# ina226-breakout.net
KiCad netlist of a schematic drawn in EAGLE
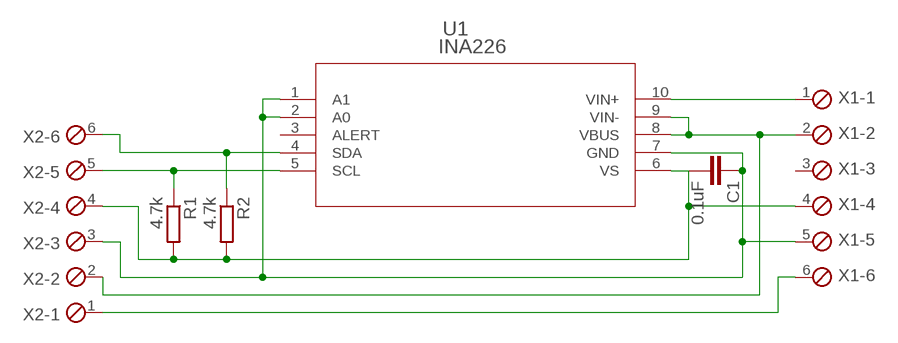
[diagram p0: schematic, sheet 1]

(export (version "E")
  (design (tool "Eeschema 10.0.6"))
  (components
    (comp (ref "C1")
      (value "0.1uF")
      (footprint "eagle-import:C0603")
      (libsource (lib "eagle-import") (part "C-EUC0603"))
    )
    (comp (ref "R1")
      (value "4.7k")
      (footprint "eagle-import:R0603")
      (libsource (lib "eagle-import") (part "R-EU_R0603"))
    )
    (comp (ref "R2")
      (value "4.7k")
      (footprint "eagle-import:R0603")
      (libsource (lib "eagle-import") (part "R-EU_R0603"))
    )
    (comp (ref "U1")
      (value "INA226")
      (footprint "eagle-import:DGS10")
      (fields
        (field (name "MANUFACTURER_PART_NUMBER") "INA226AIDGSR")
        (field (name "MANUFACTURER_PART_NUMBER_1") "INA226")
        (field (name "COPYRIGHT") "Copyright (C) 2022 Ultra Librarian. All rights reserved.")
      )
      (libsource (lib "eagle-import") (part "INA226AIDGSR"))
    )
    (comp (ref "X1")
      (value "MPT6")
      (footprint "eagle-import:6POL254")
      (libsource (lib "eagle-import") (part "MPT6"))
    )
    (comp (ref "X2")
      (value "MPT6")
      (footprint "eagle-import:6POL254")
      (libsource (lib "eagle-import") (part "MPT6"))
    )
  )
  (nets
    (net (code "1") (name "Net-(U1-A0)") (class "Default")
      (node (ref "C1") (pin "1") (pinfunction "1_1") (pintype "passive"))
      (node (ref "U1") (pin "1") (pinfunction "A1_1") (pintype "passive"))
      (node (ref "U1") (pin "2") (pinfunction "A0_2") (pintype "passive"))
      (node (ref "U1") (pin "7") (pinfunction "GND_7") (pintype "power_in"))
      (node (ref "X1") (pin "5") (pinfunction "1_5") (pintype "passive"))
      (node (ref "X2") (pin "3") (pinfunction "1_3") (pintype "passive"))
    )
    (net (code "2") (name "Net-(U1-SCL)") (class "Default")
      (node (ref "R1") (pin "1") (pinfunction "1_1") (pintype "passive"))
      (node (ref "U1") (pin "5") (pinfunction "SCL_5") (pintype "input"))
      (node (ref "X2") (pin "5") (pinfunction "1_5") (pintype "passive"))
    )
    (net (code "3") (name "Net-(U1-SDA)") (class "Default")
      (node (ref "R2") (pin "1") (pinfunction "1_1") (pintype "passive"))
      (node (ref "U1") (pin "4") (pinfunction "SDA_4") (pintype "bidirectional"))
      (node (ref "X2") (pin "6") (pinfunction "1_6") (pintype "passive"))
    )
    (net (code "4") (name "Net-(U1-VBUS)") (class "Default")
      (node (ref "U1") (pin "8") (pinfunction "VBUS_8") (pintype "input"))
      (node (ref "U1") (pin "9") (pinfunction "VIN-_9") (pintype "input"))
      (node (ref "X1") (pin "2") (pinfunction "1_2") (pintype "passive"))
      (node (ref "X2") (pin "2") (pinfunction "1_2") (pintype "passive"))
    )
    (net (code "5") (name "Net-(U1-VIN+)") (class "Default")
      (node (ref "U1") (pin "10") (pinfunction "VIN+_10") (pintype "input"))
      (node (ref "X1") (pin "1") (pinfunction "1_1") (pintype "passive"))
    )
    (net (code "6") (name "Net-(U1-VS)") (class "Default")
      (node (ref "C1") (pin "2") (pinfunction "2_2") (pintype "passive"))
      (node (ref "R1") (pin "2") (pinfunction "2_2") (pintype "passive"))
      (node (ref "R2") (pin "2") (pinfunction "2_2") (pintype "passive"))
      (node (ref "U1") (pin "6") (pinfunction "VS_6") (pintype "power_in"))
      (node (ref "X1") (pin "4") (pinfunction "1_4") (pintype "passive"))
      (node (ref "X2") (pin "4") (pinfunction "1_4") (pintype "passive"))
    )
    (net (code "7") (name "Net-(X1F-1)") (class "Default")
      (node (ref "X1") (pin "6") (pinfunction "1_6") (pintype "passive"))
      (node (ref "X2") (pin "1") (pinfunction "1_1") (pintype "passive"))
    )
    (net (code "8") (name "unconnected-(U1-ALERT-Pad3)") (class "Default")
      (node (ref "U1") (pin "3") (pinfunction "ALERT_3") (pintype "output"))
    )
    (net (code "9") (name "unconnected-(X1C-1-Pad3)") (class "Default")
      (node (ref "X1") (pin "3") (pinfunction "1_3") (pintype "passive"))
    )
  )
)
